# sensor_board_27-05.net
KiCad netlist of a schematic drawn in EAGLE
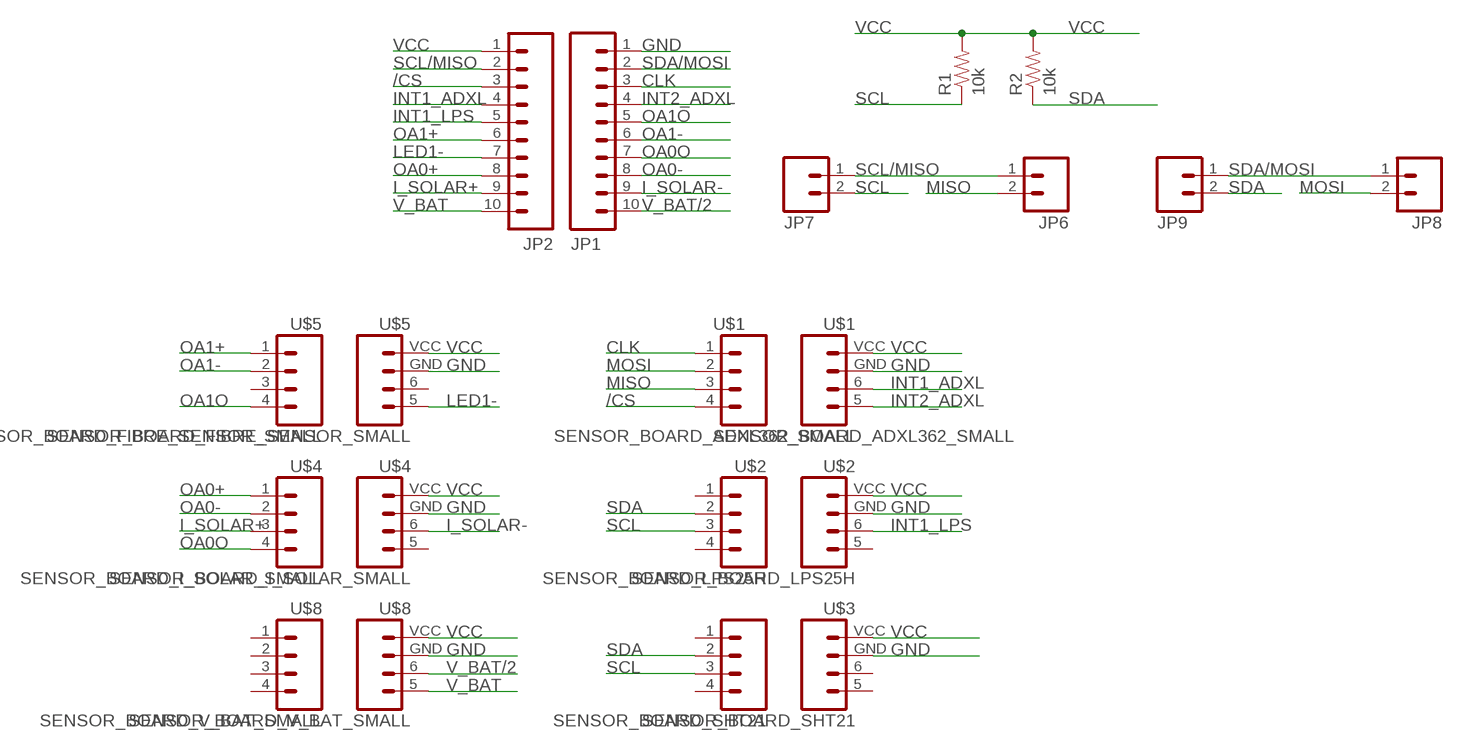
[diagram p0: schematic, sheet 1]

(export (version "E")
  (design (tool "Eeschema 10.0.6"))
  (components
    (comp (ref "JP1")
      (value "M10SILK_FEMALE_PTH")
      (footprint "eagle-import:1X10")
      (libsource (lib "eagle-import") (part "M10SILK_FEMALE_PTH"))
    )
    (comp (ref "JP2")
      (value "M10SILK_FEMALE_PTH")
      (footprint "eagle-import:1X10")
      (libsource (lib "eagle-import") (part "M10SILK_FEMALE_PTH"))
    )
    (comp (ref "JP6")
      (value "M02PTH")
      (footprint "eagle-import:1X02")
      (libsource (lib "eagle-import") (part "M02PTH"))
    )
    (comp (ref "JP7")
      (value "M02PTH")
      (footprint "eagle-import:1X02")
      (libsource (lib "eagle-import") (part "M02PTH"))
    )
    (comp (ref "JP8")
      (value "M02PTH")
      (footprint "eagle-import:1X02")
      (libsource (lib "eagle-import") (part "M02PTH"))
    )
    (comp (ref "JP9")
      (value "M02PTH")
      (footprint "eagle-import:1X02")
      (libsource (lib "eagle-import") (part "M02PTH"))
    )
    (comp (ref "R1")
      (value "10k")
      (footprint "eagle-import:AXIAL-0.3")
      (libsource (lib "eagle-import") (part "10KOHM-1/4W-1%(PTH)HORIZ"))
    )
    (comp (ref "R2")
      (value "10k")
      (footprint "eagle-import:AXIAL-0.3")
      (libsource (lib "eagle-import") (part "10KOHM-1/4W-1%(PTH)HORIZ"))
    )
    (comp (ref "U$1")
      (value "SENSOR_BOARD_ADXL362_SMALL")
      (footprint "eagle-import:SENSOR_BOARD_GEN_SMALL")
      (libsource (lib "eagle-import") (part "SENSOR_BOARD_ADXL362_SMALL"))
    )
    (comp (ref "U$2")
      (value "SENSOR_BOARD_LPS25H")
      (footprint "eagle-import:SENSOR_BOARD_GEN")
      (libsource (lib "eagle-import") (part "SENSOR_BOARD_LPS25H"))
    )
    (comp (ref "U$3")
      (value "SENSOR_BOARD_SHT21")
      (footprint "eagle-import:SENSOR_BOARD_GEN")
      (libsource (lib "eagle-import") (part "SENSOR_BOARD_SHT21"))
    )
    (comp (ref "U$4")
      (value "SENSOR_BOARD_I_SOLAR_SMALL")
      (footprint "eagle-import:SENSOR_BOARD_GEN_SMALL")
      (libsource (lib "eagle-import") (part "SENSOR_BOARD_I_SOLAR_SMALL"))
    )
    (comp (ref "U$5")
      (value "SENSOR_BOARD_FIBRE_SENSOR_SMALL")
      (footprint "eagle-import:SENSOR_BOARD_GEN_SMALL")
      (libsource (lib "eagle-import") (part "SENSOR_BOARD_FIBRE_SENSOR_SMALL"))
    )
    (comp (ref "U$8")
      (value "SENSOR_BOARD_V_BAT_SMALL")
      (footprint "eagle-import:SENSOR_BOARD_GEN_SMALL")
      (libsource (lib "eagle-import") (part "SENSOR_BOARD_V_BAT_SMALL"))
    )
  )
  (nets
    (net (code "1") (name "/CLK") (class "Default")
      (node (ref "JP1") (pin "3") (pinfunction "3_3") (pintype "passive"))
      (node (ref "U$1") (pin "1") (pinfunction "CLK_1") (pintype "passive"))
    )
    (net (code "2") (name "/GND") (class "Default")
      (node (ref "JP1") (pin "1") (pinfunction "1_1") (pintype "passive"))
      (node (ref "U$1") (pin "GND") (pinfunction "GND_GND") (pintype "passive"))
      (node (ref "U$2") (pin "GND") (pinfunction "GND_GND") (pintype "passive"))
      (node (ref "U$3") (pin "GND") (pinfunction "GND_GND") (pintype "passive"))
      (node (ref "U$4") (pin "GND") (pinfunction "GND_GND") (pintype "passive"))
      (node (ref "U$5") (pin "GND") (pinfunction "GND_GND") (pintype "passive"))
      (node (ref "U$8") (pin "GND") (pinfunction "GND_GND") (pintype "passive"))
    )
    (net (code "3") (name "/INT1_ADXL") (class "Default")
      (node (ref "JP2") (pin "4") (pinfunction "4_4") (pintype "passive"))
      (node (ref "U$1") (pin "6") (pinfunction "INT1_6") (pintype "passive"))
    )
    (net (code "4") (name "/INT1_LPS") (class "Default")
      (node (ref "JP2") (pin "5") (pinfunction "5_5") (pintype "passive"))
      (node (ref "U$2") (pin "6") (pinfunction "INT1_6") (pintype "passive"))
    )
    (net (code "5") (name "/INT2_ADXL") (class "Default")
      (node (ref "JP1") (pin "4") (pinfunction "4_4") (pintype "passive"))
      (node (ref "U$1") (pin "5") (pinfunction "INT2_5") (pintype "passive"))
    )
    (net (code "6") (name "/I_SOLAR+") (class "Default")
      (node (ref "JP2") (pin "9") (pinfunction "9_9") (pintype "passive"))
      (node (ref "U$4") (pin "3") (pinfunction "I_SOLAR+_3") (pintype "passive"))
    )
    (net (code "7") (name "/I_SOLAR-") (class "Default")
      (node (ref "JP1") (pin "9") (pinfunction "9_9") (pintype "passive"))
      (node (ref "U$4") (pin "6") (pinfunction "I_SOLAR-_6") (pintype "passive"))
    )
    (net (code "8") (name "/LED1-") (class "Default")
      (node (ref "JP2") (pin "7") (pinfunction "7_7") (pintype "passive"))
      (node (ref "U$5") (pin "5") (pinfunction "LED-_5") (pintype "passive"))
    )
    (net (code "9") (name "/MISO") (class "Default")
      (node (ref "JP6") (pin "2") (pinfunction "2_2") (pintype "passive"))
      (node (ref "U$1") (pin "3") (pinfunction "MISO_3") (pintype "passive"))
    )
    (net (code "10") (name "/MOSI") (class "Default")
      (node (ref "JP8") (pin "2") (pinfunction "2_2") (pintype "passive"))
      (node (ref "U$1") (pin "2") (pinfunction "MOSI_2") (pintype "passive"))
    )
    (net (code "11") (name "/OA0+") (class "Default")
      (node (ref "JP2") (pin "8") (pinfunction "8_8") (pintype "passive"))
      (node (ref "U$4") (pin "1") (pinfunction "OA+_1") (pintype "passive"))
    )
    (net (code "12") (name "/OA0-") (class "Default")
      (node (ref "JP1") (pin "8") (pinfunction "8_8") (pintype "passive"))
      (node (ref "U$4") (pin "2") (pinfunction "OA-_2") (pintype "passive"))
    )
    (net (code "13") (name "/OA0O") (class "Default")
      (node (ref "JP1") (pin "7") (pinfunction "7_7") (pintype "passive"))
      (node (ref "U$4") (pin "4") (pinfunction "OAO_4") (pintype "passive"))
    )
    (net (code "14") (name "/OA1+") (class "Default")
      (node (ref "JP2") (pin "6") (pinfunction "6_6") (pintype "passive"))
      (node (ref "U$5") (pin "1") (pinfunction "OA+_1") (pintype "passive"))
    )
    (net (code "15") (name "/OA1-") (class "Default")
      (node (ref "JP1") (pin "6") (pinfunction "6_6") (pintype "passive"))
      (node (ref "U$5") (pin "2") (pinfunction "OA-_2") (pintype "passive"))
    )
    (net (code "16") (name "/OA1O") (class "Default")
      (node (ref "JP1") (pin "5") (pinfunction "5_5") (pintype "passive"))
      (node (ref "U$5") (pin "4") (pinfunction "OAO_4") (pintype "passive"))
    )
    (net (code "17") (name "/SCL") (class "Default")
      (node (ref "JP7") (pin "2") (pinfunction "2_2") (pintype "passive"))
      (node (ref "R1") (pin "P$1") (pinfunction "1_P$1") (pintype "passive"))
      (node (ref "U$2") (pin "3") (pinfunction "SCL_3") (pintype "passive"))
      (node (ref "U$3") (pin "3") (pinfunction "SCL_3") (pintype "passive"))
    )
    (net (code "18") (name "/SCL{slash}MISO") (class "Default")
      (node (ref "JP2") (pin "2") (pinfunction "2_2") (pintype "passive"))
      (node (ref "JP6") (pin "1") (pinfunction "1_1") (pintype "passive"))
      (node (ref "JP7") (pin "1") (pinfunction "1_1") (pintype "passive"))
    )
    (net (code "19") (name "/SDA") (class "Default")
      (node (ref "JP9") (pin "2") (pinfunction "2_2") (pintype "passive"))
      (node (ref "R2") (pin "P$1") (pinfunction "1_P$1") (pintype "passive"))
      (node (ref "U$2") (pin "2") (pinfunction "SDA_2") (pintype "passive"))
      (node (ref "U$3") (pin "2") (pinfunction "SDA_2") (pintype "passive"))
    )
    (net (code "20") (name "/SDA{slash}MOSI") (class "Default")
      (node (ref "JP1") (pin "2") (pinfunction "2_2") (pintype "passive"))
      (node (ref "JP8") (pin "1") (pinfunction "1_1") (pintype "passive"))
      (node (ref "JP9") (pin "1") (pinfunction "1_1") (pintype "passive"))
    )
    (net (code "21") (name "/VCC") (class "Default")
      (node (ref "JP2") (pin "1") (pinfunction "1_1") (pintype "passive"))
      (node (ref "R1") (pin "P$2") (pinfunction "2_P$2") (pintype "passive"))
      (node (ref "R2") (pin "P$2") (pinfunction "2_P$2") (pintype "passive"))
      (node (ref "U$1") (pin "VCC") (pinfunction "VCC_VCC") (pintype "passive"))
      (node (ref "U$2") (pin "VCC") (pinfunction "VCC_VCC") (pintype "passive"))
      (node (ref "U$3") (pin "VCC") (pinfunction "VCC_VCC") (pintype "passive"))
      (node (ref "U$4") (pin "VCC") (pinfunction "VCC_VCC") (pintype "passive"))
      (node (ref "U$5") (pin "VCC") (pinfunction "VCC_VCC") (pintype "passive"))
      (node (ref "U$8") (pin "VCC") (pinfunction "VCC_VCC") (pintype "passive"))
    )
    (net (code "22") (name "/V_BAT") (class "Default")
      (node (ref "JP2") (pin "10") (pinfunction "10_10") (pintype "passive"))
      (node (ref "U$8") (pin "5") (pinfunction "V_BAT_5") (pintype "passive"))
    )
    (net (code "23") (name "/V_BAT{slash}2") (class "Default")
      (node (ref "JP1") (pin "10") (pinfunction "10_10") (pintype "passive"))
      (node (ref "U$8") (pin "6") (pinfunction "V_BAT/2_6") (pintype "passive"))
    )
    (net (code "24") (name "/{slash}CS") (class "Default")
      (node (ref "JP2") (pin "3") (pinfunction "3_3") (pintype "passive"))
      (node (ref "U$1") (pin "4") (pinfunction "/CS_4") (pintype "passive"))
    )
    (net (code "25") (name "unconnected-(U$2-Pad1)") (class "Default")
      (node (ref "U$2") (pin "1") (pinfunction "1_1") (pintype "passive"))
    )
    (net (code "26") (name "unconnected-(U$2-Pad4)") (class "Default")
      (node (ref "U$2") (pin "4") (pinfunction "4_4") (pintype "passive"))
    )
    (net (code "27") (name "unconnected-(U$2-Pad5)") (class "Default")
      (node (ref "U$2") (pin "5") (pinfunction "5_5") (pintype "passive"))
    )
    (net (code "28") (name "unconnected-(U$3-Pad1)") (class "Default")
      (node (ref "U$3") (pin "1") (pinfunction "1_1") (pintype "passive"))
    )
    (net (code "29") (name "unconnected-(U$3-Pad4)") (class "Default")
      (node (ref "U$3") (pin "4") (pinfunction "4_4") (pintype "passive"))
    )
    (net (code "30") (name "unconnected-(U$3-Pad5)") (class "Default")
      (node (ref "U$3") (pin "5") (pinfunction "5_5") (pintype "passive"))
    )
    (net (code "31") (name "unconnected-(U$3-Pad6)") (class "Default")
      (node (ref "U$3") (pin "6") (pinfunction "6_6") (pintype "passive"))
    )
    (net (code "32") (name "unconnected-(U$4-Pad5)") (class "Default")
      (node (ref "U$4") (pin "5") (pinfunction "5_5") (pintype "passive"))
    )
    (net (code "33") (name "unconnected-(U$5-Pad3)") (class "Default")
      (node (ref "U$5") (pin "3") (pinfunction "3_3") (pintype "passive"))
    )
    (net (code "34") (name "unconnected-(U$5-Pad6)") (class "Default")
      (node (ref "U$5") (pin "6") (pinfunction "6_6") (pintype "passive"))
    )
    (net (code "35") (name "unconnected-(U$8-Pad1)") (class "Default")
      (node (ref "U$8") (pin "1") (pinfunction "1_1") (pintype "passive"))
    )
    (net (code "36") (name "unconnected-(U$8-Pad2)") (class "Default")
      (node (ref "U$8") (pin "2") (pinfunction "2_2") (pintype "passive"))
    )
    (net (code "37") (name "unconnected-(U$8-Pad3)") (class "Default")
      (node (ref "U$8") (pin "3") (pinfunction "3_3") (pintype "passive"))
    )
    (net (code "38") (name "unconnected-(U$8-Pad4)") (class "Default")
      (node (ref "U$8") (pin "4") (pinfunction "4_4") (pintype "passive"))
    )
  )
)
